# TalonSRXBreakoutV1.net
KiCad netlist of a schematic drawn in EAGLE
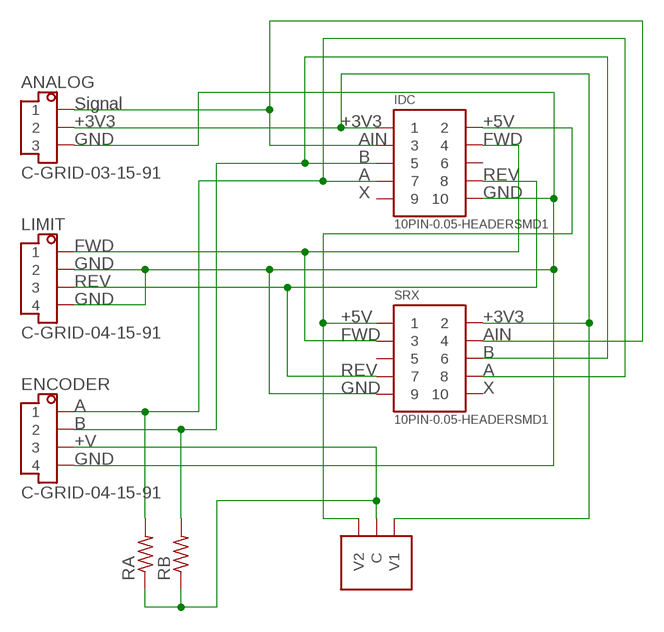
[diagram p0: schematic, sheet 1]

(export (version "E")
  (design (tool "Eeschema 10.0.6"))
  (components
    (comp (ref "ANALOG")
      (value "C-GRID-03-15-91")
      (footprint "eagle-import:15-91-03")
      (libsource (lib "eagle-import") (part "C-GRID-03-15-91"))
    )
    (comp (ref "ENCODER")
      (value "C-GRID-04-15-91")
      (footprint "eagle-import:15-91-04")
      (libsource (lib "eagle-import") (part "C-GRID-04-15-91"))
    )
    (comp (ref "IDC")
      (value "10PIN-0.05-HEADERSMD1")
      (footprint "eagle-import:1.27-10PIN")
      (libsource (lib "eagle-import") (part "10PIN-0.05-HEADERSMD1"))
    )
    (comp (ref "LIMIT")
      (value "C-GRID-04-15-91")
      (footprint "eagle-import:15-91-04")
      (libsource (lib "eagle-import") (part "C-GRID-04-15-91"))
    )
    (comp (ref "RA")
      (value "R-US_R0805")
      (footprint "eagle-import:R0805")
      (libsource (lib "eagle-import") (part "R-US_R0805"))
    )
    (comp (ref "RB")
      (value "R-US_R0805")
      (footprint "eagle-import:R0805")
      (libsource (lib "eagle-import") (part "R-US_R0805"))
    )
    (comp (ref "SRX")
      (value "10PIN-0.05-HEADERSMD1")
      (footprint "eagle-import:1.27-10PIN")
      (libsource (lib "eagle-import") (part "10PIN-0.05-HEADERSMD1"))
    )
    (comp (ref "U$1")
      (value "3PIN-RA-VSELECT")
      (footprint "eagle-import:2.54-3PIN-SMD-RA")
      (libsource (lib "eagle-import") (part "3PIN-RA-VSELECT"))
    )
  )
  (nets
    (net (code "1") (name "Net-(IDC-1)") (class "Default")
      (node (ref "ANALOG") (pin "2") (pinfunction "2_2") (pintype "passive"))
      (node (ref "IDC") (pin "P1") (pinfunction "1_P1") (pintype "bidirectional"))
      (node (ref "SRX") (pin "P2") (pinfunction "2_P2") (pintype "bidirectional"))
      (node (ref "U$1") (pin "P1") (pinfunction "V1_P1") (pintype "bidirectional"))
    )
    (net (code "2") (name "Net-(IDC-2)") (class "Default")
      (node (ref "IDC") (pin "P2") (pinfunction "2_P2") (pintype "bidirectional"))
      (node (ref "SRX") (pin "P1") (pinfunction "1_P1") (pintype "bidirectional"))
      (node (ref "U$1") (pin "P3") (pinfunction "V2_P3") (pintype "bidirectional"))
    )
    (net (code "3") (name "Net-(IDC-3)") (class "Default")
      (node (ref "ANALOG") (pin "1") (pinfunction "1_1") (pintype "passive"))
      (node (ref "IDC") (pin "P3") (pinfunction "3_P3") (pintype "bidirectional"))
      (node (ref "SRX") (pin "P4") (pinfunction "4_P4") (pintype "bidirectional"))
    )
    (net (code "4") (name "Net-(IDC-4)") (class "Default")
      (node (ref "IDC") (pin "P4") (pinfunction "4_P4") (pintype "bidirectional"))
      (node (ref "LIMIT") (pin "1") (pinfunction "1_1") (pintype "passive"))
      (node (ref "SRX") (pin "P3") (pinfunction "3_P3") (pintype "bidirectional"))
    )
    (net (code "5") (name "Net-(IDC-5)") (class "Default")
      (node (ref "ENCODER") (pin "2") (pinfunction "2_2") (pintype "passive"))
      (node (ref "IDC") (pin "P5") (pinfunction "5_P5") (pintype "bidirectional"))
      (node (ref "RB") (pin "2") (pinfunction "2_2") (pintype "passive"))
      (node (ref "SRX") (pin "P6") (pinfunction "6_P6") (pintype "bidirectional"))
    )
    (net (code "6") (name "Net-(IDC-7)") (class "Default")
      (node (ref "ENCODER") (pin "1") (pinfunction "1_1") (pintype "passive"))
      (node (ref "IDC") (pin "P7") (pinfunction "7_P7") (pintype "bidirectional"))
      (node (ref "RA") (pin "2") (pinfunction "2_2") (pintype "passive"))
      (node (ref "SRX") (pin "P8") (pinfunction "8_P8") (pintype "bidirectional"))
    )
    (net (code "7") (name "Net-(IDC-8)") (class "Default")
      (node (ref "IDC") (pin "P8") (pinfunction "8_P8") (pintype "bidirectional"))
      (node (ref "LIMIT") (pin "3") (pinfunction "3_3") (pintype "passive"))
      (node (ref "SRX") (pin "P7") (pinfunction "7_P7") (pintype "bidirectional"))
    )
    (net (code "8") (name "Net-(IDC-10)") (class "Default")
      (node (ref "ANALOG") (pin "3") (pinfunction "3_3") (pintype "passive"))
      (node (ref "ENCODER") (pin "4") (pinfunction "4_4") (pintype "passive"))
      (node (ref "IDC") (pin "P10") (pinfunction "10_P10") (pintype "bidirectional"))
      (node (ref "LIMIT") (pin "2") (pinfunction "2_2") (pintype "passive"))
      (node (ref "LIMIT") (pin "4") (pinfunction "4_4") (pintype "passive"))
      (node (ref "SRX") (pin "P9") (pinfunction "9_P9") (pintype "bidirectional"))
    )
    (net (code "9") (name "Net-(U$1-C)") (class "Default")
      (node (ref "ENCODER") (pin "3") (pinfunction "3_3") (pintype "passive"))
      (node (ref "RA") (pin "1") (pinfunction "1_1") (pintype "passive"))
      (node (ref "RB") (pin "1") (pinfunction "1_1") (pintype "passive"))
      (node (ref "U$1") (pin "P2") (pinfunction "C_P2") (pintype "bidirectional"))
    )
    (net (code "10") (name "unconnected-(IDC-6-PadP6)") (class "Default")
      (node (ref "IDC") (pin "P6") (pinfunction "6_P6") (pintype "bidirectional"))
    )
    (net (code "11") (name "unconnected-(IDC-9-PadP9)") (class "Default")
      (node (ref "IDC") (pin "P9") (pinfunction "9_P9") (pintype "bidirectional"))
    )
    (net (code "12") (name "unconnected-(SRX-5-PadP5)") (class "Default")
      (node (ref "SRX") (pin "P5") (pinfunction "5_P5") (pintype "bidirectional"))
    )
    (net (code "13") (name "unconnected-(SRX-10-PadP10)") (class "Default")
      (node (ref "SRX") (pin "P10") (pinfunction "10_P10") (pintype "bidirectional"))
    )
  )
)
